# T01_Synth_Glove_v3_1.net
KiCad netlist of a schematic drawn in EAGLE
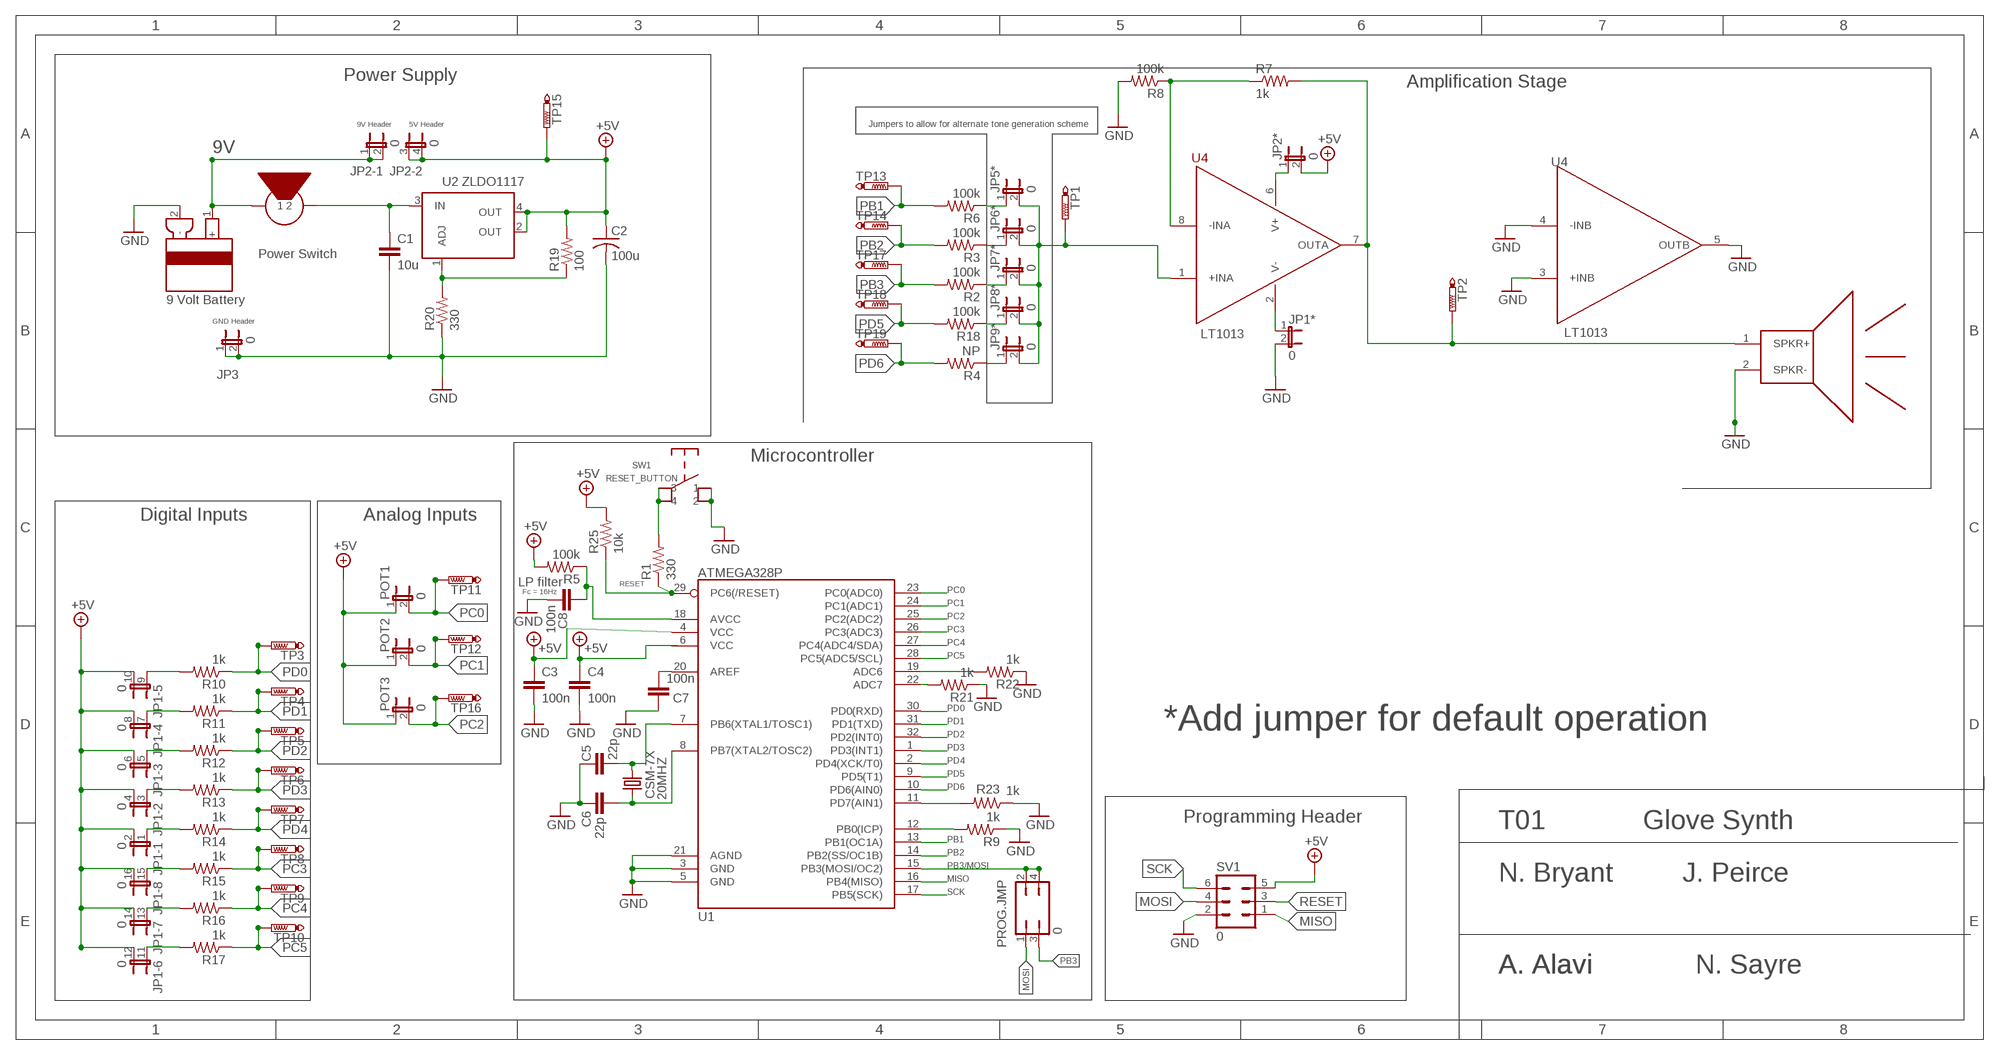
[diagram p0: schematic, sheet 1]

(export (version "E")
  (design (tool "Eeschema 10.0.6"))
  (components
    (comp (ref "20MHZ")
      (value "CSM-7X")
      (footprint "eagle-import:CSM-7X-DU")
      (libsource (lib "eagle-import") (part "CSM-7X-DU"))
    )
    (comp (ref "C1")
      (value "10u")
      (footprint "eagle-import:0603-CAP")
      (libsource (lib "eagle-import") (part "CAP0603-CAP"))
    )
    (comp (ref "C2")
      (value "100u")
      (footprint "eagle-import:C075-042X103")
      (libsource (lib "eagle-import") (part "C-US075-042X103"))
    )
    (comp (ref "C3")
      (value "100n")
      (footprint "eagle-import:0603-CAP")
      (libsource (lib "eagle-import") (part "CAP0603-CAP"))
    )
    (comp (ref "C4")
      (value "100n")
      (footprint "eagle-import:0603-CAP")
      (libsource (lib "eagle-import") (part "CAP0603-CAP"))
    )
    (comp (ref "C5")
      (value "22p")
      (footprint "eagle-import:0603-CAP")
      (libsource (lib "eagle-import") (part "CAP0603-CAP"))
    )
    (comp (ref "C6")
      (value "22p")
      (footprint "eagle-import:0603-CAP")
      (libsource (lib "eagle-import") (part "CAP0603-CAP"))
    )
    (comp (ref "C7")
      (value "100n")
      (footprint "eagle-import:0603-CAP")
      (libsource (lib "eagle-import") (part "CAP0603-CAP"))
    )
    (comp (ref "C8")
      (value "100n")
      (footprint "eagle-import:0603-CAP")
      (libsource (lib "eagle-import") (part "CAP0603-CAP"))
    )
    (comp (ref "JP1")
      (value "0")
      (footprint "eagle-import:JP8Q")
      (libsource (lib "eagle-import") (part "JP8QE"))
    )
    (comp (ref "JP1*")
      (value "0")
      (footprint "eagle-import:JP1")
      (libsource (lib "eagle-import") (part "JP1E"))
    )
    (comp (ref "JP2")
      (value "0")
      (footprint "eagle-import:JP2Q")
      (libsource (lib "eagle-import") (part "JP2QE"))
    )
    (comp (ref "JP2*")
      (value "0")
      (footprint "eagle-import:JP1")
      (libsource (lib "eagle-import") (part "JP1E"))
    )
    (comp (ref "JP3")
      (value "0")
      (footprint "eagle-import:JP1")
      (libsource (lib "eagle-import") (part "JP1E"))
    )
    (comp (ref "JP5*")
      (value "0")
      (footprint "eagle-import:JP1")
      (libsource (lib "eagle-import") (part "JP1E"))
    )
    (comp (ref "JP6*")
      (value "0")
      (footprint "eagle-import:JP1")
      (libsource (lib "eagle-import") (part "JP1E"))
    )
    (comp (ref "JP7*")
      (value "0")
      (footprint "eagle-import:JP1")
      (libsource (lib "eagle-import") (part "JP1E"))
    )
    (comp (ref "JP8*")
      (value "0")
      (footprint "eagle-import:JP1")
      (libsource (lib "eagle-import") (part "JP1E"))
    )
    (comp (ref "JP9*")
      (value "0")
      (footprint "eagle-import:JP1")
      (libsource (lib "eagle-import") (part "JP1E"))
    )
    (comp (ref "POT1")
      (value "0")
      (footprint "eagle-import:JP1")
      (libsource (lib "eagle-import") (part "JP1E"))
    )
    (comp (ref "POT2")
      (value "0")
      (footprint "eagle-import:JP1")
      (libsource (lib "eagle-import") (part "JP1E"))
    )
    (comp (ref "POT3")
      (value "0")
      (footprint "eagle-import:JP1")
      (libsource (lib "eagle-import") (part "JP1E"))
    )
    (comp (ref "PROG.JMP")
      (value "0")
      (footprint "eagle-import:JP2Q")
      (libsource (lib "eagle-import") (part "JP2Q"))
    )
    (comp (ref "R1")
      (value "330")
      (footprint "eagle-import:0603-RES")
      (libsource (lib "eagle-import") (part "RESISTOR0603"))
    )
    (comp (ref "R2")
      (value "100k")
      (footprint "eagle-import:0603-RES")
      (libsource (lib "eagle-import") (part "RESISTOR0603"))
    )
    (comp (ref "R3")
      (value "100k")
      (footprint "eagle-import:0603-RES")
      (libsource (lib "eagle-import") (part "RESISTOR0603"))
    )
    (comp (ref "R4")
      (value "NP")
      (footprint "eagle-import:0603-RES")
      (libsource (lib "eagle-import") (part "RESISTOR0603"))
    )
    (comp (ref "R5")
      (value "100k")
      (footprint "eagle-import:0603-RES")
      (libsource (lib "eagle-import") (part "RESISTOR0603"))
    )
    (comp (ref "R6")
      (value "100k")
      (footprint "eagle-import:0603-RES")
      (libsource (lib "eagle-import") (part "RESISTOR0603"))
    )
    (comp (ref "R7")
      (value "1k")
      (footprint "eagle-import:0603-RES")
      (libsource (lib "eagle-import") (part "RESISTOR0603"))
    )
    (comp (ref "R8")
      (value "100k")
      (footprint "eagle-import:0603-RES")
      (libsource (lib "eagle-import") (part "RESISTOR0603"))
    )
    (comp (ref "R9")
      (value "1k")
      (footprint "eagle-import:0603-RES")
      (libsource (lib "eagle-import") (part "RESISTOR0603"))
    )
    (comp (ref "R10")
      (value "1k")
      (footprint "eagle-import:0603-RES")
      (libsource (lib "eagle-import") (part "RESISTOR0603"))
    )
    (comp (ref "R11")
      (value "1k")
      (footprint "eagle-import:0603-RES")
      (libsource (lib "eagle-import") (part "RESISTOR0603"))
    )
    (comp (ref "R12")
      (value "1k")
      (footprint "eagle-import:0603-RES")
      (libsource (lib "eagle-import") (part "RESISTOR0603"))
    )
    (comp (ref "R13")
      (value "1k")
      (footprint "eagle-import:0603-RES")
      (libsource (lib "eagle-import") (part "RESISTOR0603"))
    )
    (comp (ref "R14")
      (value "1k")
      (footprint "eagle-import:0603-RES")
      (libsource (lib "eagle-import") (part "RESISTOR0603"))
    )
    (comp (ref "R15")
      (value "1k")
      (footprint "eagle-import:0603-RES")
      (libsource (lib "eagle-import") (part "RESISTOR0603"))
    )
    (comp (ref "R16")
      (value "1k")
      (footprint "eagle-import:0603-RES")
      (libsource (lib "eagle-import") (part "RESISTOR0603"))
    )
    (comp (ref "R17")
      (value "1k")
      (footprint "eagle-import:0603-RES")
      (libsource (lib "eagle-import") (part "RESISTOR0603"))
    )
    (comp (ref "R18")
      (value "100k")
      (footprint "eagle-import:0603-RES")
      (libsource (lib "eagle-import") (part "RESISTOR0603"))
    )
    (comp (ref "R19")
      (value "100")
      (footprint "eagle-import:0603-RES")
      (libsource (lib "eagle-import") (part "RESISTOR0603"))
    )
    (comp (ref "R20")
      (value "330")
      (footprint "eagle-import:0603-RES")
      (libsource (lib "eagle-import") (part "RESISTOR0603"))
    )
    (comp (ref "R21")
      (value "1k")
      (footprint "eagle-import:0603-RES")
      (libsource (lib "eagle-import") (part "RESISTOR0603"))
    )
    (comp (ref "R22")
      (value "1k")
      (footprint "eagle-import:0603-RES")
      (libsource (lib "eagle-import") (part "RESISTOR0603"))
    )
    (comp (ref "R23")
      (value "1k")
      (footprint "eagle-import:0603-RES")
      (libsource (lib "eagle-import") (part "RESISTOR0603"))
    )
    (comp (ref "R25")
      (value "10k")
      (footprint "eagle-import:0603-RES")
      (libsource (lib "eagle-import") (part "RESISTOR0603"))
    )
    (comp (ref "SV1")
      (value "0")
      (footprint "eagle-import:MA03-2")
      (libsource (lib "eagle-import") (part "MA03-2"))
    )
    (comp (ref "SW1")
      (value "RESET_BUTTON")
      (footprint "eagle-import:RESET_BUTTON")
      (libsource (lib "eagle-import") (part "RESET_BUTTON"))
    )
    (comp (ref "TP1")
      (value "PTR1B2,54")
      (footprint "eagle-import:B2,54")
      (libsource (lib "eagle-import") (part "PTR1B2,54"))
    )
    (comp (ref "TP2")
      (value "PTR1B2,54")
      (footprint "eagle-import:B2,54")
      (libsource (lib "eagle-import") (part "PTR1B2,54"))
    )
    (comp (ref "TP3")
      (value "PTR1B2,54")
      (footprint "eagle-import:B2,54")
      (libsource (lib "eagle-import") (part "PTR1B2,54"))
    )
    (comp (ref "TP4")
      (value "PTR1B2,54")
      (footprint "eagle-import:B2,54")
      (libsource (lib "eagle-import") (part "PTR1B2,54"))
    )
    (comp (ref "TP5")
      (value "PTR1B2,54")
      (footprint "eagle-import:B2,54")
      (libsource (lib "eagle-import") (part "PTR1B2,54"))
    )
    (comp (ref "TP6")
      (value "PTR1B2,54")
      (footprint "eagle-import:B2,54")
      (libsource (lib "eagle-import") (part "PTR1B2,54"))
    )
    (comp (ref "TP7")
      (value "PTR1B2,54")
      (footprint "eagle-import:B2,54")
      (libsource (lib "eagle-import") (part "PTR1B2,54"))
    )
    (comp (ref "TP8")
      (value "PTR1B2,54")
      (footprint "eagle-import:B2,54")
      (libsource (lib "eagle-import") (part "PTR1B2,54"))
    )
    (comp (ref "TP9")
      (value "PTR1B2,54")
      (footprint "eagle-import:B2,54")
      (libsource (lib "eagle-import") (part "PTR1B2,54"))
    )
    (comp (ref "TP10")
      (value "PTR1B2,54")
      (footprint "eagle-import:B2,54")
      (libsource (lib "eagle-import") (part "PTR1B2,54"))
    )
    (comp (ref "TP11")
      (value "PTR1B2,54")
      (footprint "eagle-import:B2,54")
      (libsource (lib "eagle-import") (part "PTR1B2,54"))
    )
    (comp (ref "TP12")
      (value "PTR1B2,54")
      (footprint "eagle-import:B2,54")
      (libsource (lib "eagle-import") (part "PTR1B2,54"))
    )
    (comp (ref "TP13")
      (value "PTR1B2,54")
      (footprint "eagle-import:B2,54")
      (libsource (lib "eagle-import") (part "PTR1B2,54"))
    )
    (comp (ref "TP14")
      (value "PTR1B2,54")
      (footprint "eagle-import:B2,54")
      (libsource (lib "eagle-import") (part "PTR1B2,54"))
    )
    (comp (ref "TP15")
      (value "PTR1B2,54")
      (footprint "eagle-import:B2,54")
      (libsource (lib "eagle-import") (part "PTR1B2,54"))
    )
    (comp (ref "TP16")
      (value "PTR1B2,54")
      (footprint "eagle-import:B2,54")
      (libsource (lib "eagle-import") (part "PTR1B2,54"))
    )
    (comp (ref "TP17")
      (value "PTR1B2,54")
      (footprint "eagle-import:B2,54")
      (libsource (lib "eagle-import") (part "PTR1B2,54"))
    )
    (comp (ref "TP18")
      (value "PTR1B2,54")
      (footprint "eagle-import:B2,54")
      (libsource (lib "eagle-import") (part "PTR1B2,54"))
    )
    (comp (ref "TP19")
      (value "PTR1B2,54")
      (footprint "eagle-import:B2,54")
      (libsource (lib "eagle-import") (part "PTR1B2,54"))
    )
    (comp (ref "U$1")
      (value "SPEAKER")
      (footprint "eagle-import:JP1")
      (libsource (lib "eagle-import") (part "SPEAKER"))
    )
    (comp (ref "U$7")
      (value "POWER_SWITCH")
      (footprint "eagle-import:JP1")
      (libsource (lib "eagle-import") (part "POWER_SWITCH"))
    )
    (comp (ref "U$8")
      (value "9VOLTBATTERY")
      (footprint "eagle-import:JP1")
      (libsource (lib "eagle-import") (part "9VOLTBATTERY"))
    )
    (comp (ref "U1")
      (value "ATMEGA328P")
      (footprint "eagle-import:TQFP32-08")
      (libsource (lib "eagle-import") (part "ATMEGA328_SMT"))
    )
    (comp (ref "U2")
      (value "ZLDO1117")
      (footprint "eagle-import:SOT223")
      (libsource (lib "eagle-import") (part "ZLDO1117"))
    )
    (comp (ref "U4")
      (value "LT1013")
      (footprint "eagle-import:SO08")
      (libsource (lib "eagle-import") (part "LT1013"))
    )
  )
  (nets
    (net (code "1") (name "+5V") (class "Default")
      (node (ref "C2") (pin "1") (pinfunction "1_1") (pintype "passive"))
      (node (ref "C3") (pin "1") (pinfunction "1_1") (pintype "passive"))
      (node (ref "C4") (pin "1") (pinfunction "1_1") (pintype "passive"))
      (node (ref "JP1") (pin "10") (pinfunction "2_10") (pintype "passive"))
      (node (ref "JP1") (pin "12") (pinfunction "2_12") (pintype "passive"))
      (node (ref "JP1") (pin "14") (pinfunction "2_14") (pintype "passive"))
      (node (ref "JP1") (pin "16") (pinfunction "2_16") (pintype "passive"))
      (node (ref "JP1") (pin "2") (pinfunction "2_2") (pintype "passive"))
      (node (ref "JP1") (pin "4") (pinfunction "2_4") (pintype "passive"))
      (node (ref "JP1") (pin "6") (pinfunction "2_6") (pintype "passive"))
      (node (ref "JP1") (pin "8") (pinfunction "2_8") (pintype "passive"))
      (node (ref "JP2") (pin "3") (pinfunction "1_3") (pintype "passive"))
      (node (ref "JP2") (pin "4") (pinfunction "2_4") (pintype "passive"))
      (node (ref "JP2*") (pin "2") (pinfunction "2_2") (pintype "passive"))
      (node (ref "POT1") (pin "1") (pinfunction "1_1") (pintype "passive"))
      (node (ref "POT2") (pin "1") (pinfunction "1_1") (pintype "passive"))
      (node (ref "POT3") (pin "1") (pinfunction "1_1") (pintype "passive"))
      (node (ref "R19") (pin "2") (pinfunction "2_2") (pintype "passive"))
      (node (ref "R25") (pin "2") (pinfunction "2_2") (pintype "passive"))
      (node (ref "R5") (pin "2") (pinfunction "2_2") (pintype "passive"))
      (node (ref "SV1") (pin "5") (pinfunction "5_5") (pintype "passive"))
      (node (ref "TP15") (pin "TP") (pinfunction "TP_TP") (pintype "input"))
      (node (ref "U1") (pin "4") (pinfunction "VCC_4") (pintype "bidirectional"))
      (node (ref "U2") (pin "2") (pinfunction "OUT_2") (pintype "bidirectional"))
      (node (ref "U2") (pin "4") (pinfunction "OUT_4") (pintype "bidirectional"))
    )
    (net (code "2") (name "/9V") (class "Default")
      (node (ref "JP2") (pin "1") (pinfunction "1_1") (pintype "passive"))
      (node (ref "JP2") (pin "2") (pinfunction "2_2") (pintype "passive"))
      (node (ref "U$7") (pin "1") (pinfunction "1_1") (pintype "bidirectional"))
      (node (ref "U$8") (pin "1") (pinfunction "+_1") (pintype "bidirectional"))
    )
    (net (code "3") (name "/PB3{slash}MOSI") (class "Default")
      (node (ref "PROG.JMP") (pin "2") (pinfunction "2_2") (pintype "passive"))
      (node (ref "PROG.JMP") (pin "4") (pinfunction "4_4") (pintype "passive"))
      (node (ref "U1") (pin "15") (pinfunction "PB3(MOSI/OC2)_15") (pintype "bidirectional"))
    )
    (net (code "4") (name "GND") (class "Default")
      (node (ref "C1") (pin "2") (pinfunction "2_2") (pintype "passive"))
      (node (ref "C2") (pin "2") (pinfunction "2_2") (pintype "passive"))
      (node (ref "C3") (pin "2") (pinfunction "2_2") (pintype "passive"))
      (node (ref "C4") (pin "2") (pinfunction "2_2") (pintype "passive"))
      (node (ref "C5") (pin "2") (pinfunction "2_2") (pintype "passive"))
      (node (ref "C6") (pin "2") (pinfunction "2_2") (pintype "passive"))
      (node (ref "C7") (pin "2") (pinfunction "2_2") (pintype "passive"))
      (node (ref "C8") (pin "2") (pinfunction "2_2") (pintype "passive"))
      (node (ref "JP1*") (pin "2") (pinfunction "2_2") (pintype "passive"))
      (node (ref "JP3") (pin "1") (pinfunction "1_1") (pintype "passive"))
      (node (ref "JP3") (pin "2") (pinfunction "2_2") (pintype "passive"))
      (node (ref "R20") (pin "1") (pinfunction "1_1") (pintype "passive"))
      (node (ref "R21") (pin "1") (pinfunction "1_1") (pintype "passive"))
      (node (ref "R22") (pin "1") (pinfunction "1_1") (pintype "passive"))
      (node (ref "R23") (pin "1") (pinfunction "1_1") (pintype "passive"))
      (node (ref "R8") (pin "2") (pinfunction "2_2") (pintype "passive"))
      (node (ref "R9") (pin "1") (pinfunction "1_1") (pintype "passive"))
      (node (ref "SV1") (pin "2") (pinfunction "2_2") (pintype "passive"))
      (node (ref "SW1") (pin "1") (pinfunction "1_1") (pintype "bidirectional"))
      (node (ref "SW1") (pin "2") (pinfunction "2_2") (pintype "bidirectional"))
      (node (ref "U$1") (pin "2") (pinfunction "SPKR-_2") (pintype "bidirectional"))
      (node (ref "U$8") (pin "2") (pinfunction "-_2") (pintype "bidirectional"))
      (node (ref "U1") (pin "21") (pinfunction "AGND_21") (pintype "bidirectional"))
      (node (ref "U1") (pin "3") (pinfunction "GND_3") (pintype "bidirectional"))
      (node (ref "U1") (pin "5") (pinfunction "GND_5") (pintype "bidirectional"))
      (node (ref "U4") (pin "3") (pinfunction "+INB_3") (pintype "bidirectional"))
      (node (ref "U4") (pin "4") (pinfunction "-INB_4") (pintype "bidirectional"))
      (node (ref "U4") (pin "5") (pinfunction "OUTB_5") (pintype "bidirectional"))
    )
    (net (code "5") (name "MISO") (class "Default")
      (node (ref "SV1") (pin "1") (pinfunction "1_1") (pintype "passive"))
      (node (ref "U1") (pin "16") (pinfunction "PB4(MISO)_16") (pintype "bidirectional"))
    )
    (net (code "6") (name "MOSI") (class "Default")
      (node (ref "PROG.JMP") (pin "1") (pinfunction "1_1") (pintype "passive"))
      (node (ref "SV1") (pin "4") (pinfunction "4_4") (pintype "passive"))
    )
    (net (code "7") (name "Net-(JP1-Pad1)") (class "Default")
      (node (ref "JP1") (pin "1") (pinfunction "1_1") (pintype "passive"))
      (node (ref "R14") (pin "2") (pinfunction "2_2") (pintype "passive"))
    )
    (net (code "8") (name "Net-(JP1B-1)") (class "Default")
      (node (ref "JP1") (pin "3") (pinfunction "1_3") (pintype "passive"))
      (node (ref "R13") (pin "2") (pinfunction "2_2") (pintype "passive"))
    )
    (net (code "9") (name "Net-(JP1C-1)") (class "Default")
      (node (ref "JP1") (pin "5") (pinfunction "1_5") (pintype "passive"))
      (node (ref "R12") (pin "2") (pinfunction "2_2") (pintype "passive"))
    )
    (net (code "10") (name "Net-(JP1D-1)") (class "Default")
      (node (ref "JP1") (pin "7") (pinfunction "1_7") (pintype "passive"))
      (node (ref "R11") (pin "2") (pinfunction "2_2") (pintype "passive"))
    )
    (net (code "11") (name "Net-(JP1E-1)") (class "Default")
      (node (ref "JP1") (pin "9") (pinfunction "1_9") (pintype "passive"))
      (node (ref "R10") (pin "2") (pinfunction "2_2") (pintype "passive"))
    )
    (net (code "12") (name "Net-(JP1F-1)") (class "Default")
      (node (ref "JP1") (pin "11") (pinfunction "1_11") (pintype "passive"))
      (node (ref "R17") (pin "2") (pinfunction "2_2") (pintype "passive"))
    )
    (net (code "13") (name "Net-(JP1G-1)") (class "Default")
      (node (ref "JP1") (pin "13") (pinfunction "1_13") (pintype "passive"))
      (node (ref "R16") (pin "2") (pinfunction "2_2") (pintype "passive"))
    )
    (net (code "14") (name "Net-(JP1H-1)") (class "Default")
      (node (ref "JP1") (pin "15") (pinfunction "1_15") (pintype "passive"))
      (node (ref "R15") (pin "2") (pinfunction "2_2") (pintype "passive"))
    )
    (net (code "15") (name "Net-(JP5*-Pad1)") (class "Default")
      (node (ref "JP5*") (pin "1") (pinfunction "1_1") (pintype "passive"))
      (node (ref "R6") (pin "1") (pinfunction "1_1") (pintype "passive"))
    )
    (net (code "16") (name "Net-(JP6*-Pad1)") (class "Default")
      (node (ref "JP6*") (pin "1") (pinfunction "1_1") (pintype "passive"))
      (node (ref "R3") (pin "1") (pinfunction "1_1") (pintype "passive"))
    )
    (net (code "17") (name "Net-(JP7*-Pad1)") (class "Default")
      (node (ref "JP7*") (pin "1") (pinfunction "1_1") (pintype "passive"))
      (node (ref "R2") (pin "1") (pinfunction "1_1") (pintype "passive"))
    )
    (net (code "18") (name "Net-(JP8*-Pad1)") (class "Default")
      (node (ref "JP8*") (pin "1") (pinfunction "1_1") (pintype "passive"))
      (node (ref "R18") (pin "1") (pinfunction "1_1") (pintype "passive"))
    )
    (net (code "19") (name "Net-(JP9*-Pad1)") (class "Default")
      (node (ref "JP9*") (pin "1") (pinfunction "1_1") (pintype "passive"))
      (node (ref "R4") (pin "1") (pinfunction "1_1") (pintype "passive"))
    )
    (net (code "20") (name "Net-(R1-Pad2)") (class "Default")
      (node (ref "R1") (pin "2") (pinfunction "2_2") (pintype "passive"))
      (node (ref "SW1") (pin "3") (pinfunction "3_3") (pintype "bidirectional"))
      (node (ref "SW1") (pin "4") (pinfunction "4_4") (pintype "bidirectional"))
    )
    (net (code "21") (name "Net-(U$1-SPKR+)") (class "Default")
      (node (ref "R7") (pin "2") (pinfunction "2_2") (pintype "passive"))
      (node (ref "TP2") (pin "TP") (pinfunction "TP_TP") (pintype "input"))
      (node (ref "U$1") (pin "1") (pinfunction "SPKR+_1") (pintype "bidirectional"))
      (node (ref "U4") (pin "7") (pinfunction "OUTA_7") (pintype "bidirectional"))
    )
    (net (code "22") (name "Net-(U1-ADC6)") (class "Default")
      (node (ref "R22") (pin "2") (pinfunction "2_2") (pintype "passive"))
      (node (ref "U1") (pin "19") (pinfunction "ADC6_19") (pintype "bidirectional"))
    )
    (net (code "23") (name "Net-(U1-ADC7)") (class "Default")
      (node (ref "R21") (pin "2") (pinfunction "2_2") (pintype "passive"))
      (node (ref "U1") (pin "22") (pinfunction "ADC7_22") (pintype "bidirectional"))
    )
    (net (code "24") (name "Net-(U1-AREF)") (class "Default")
      (node (ref "C7") (pin "1") (pinfunction "1_1") (pintype "passive"))
      (node (ref "U1") (pin "20") (pinfunction "AREF_20") (pintype "bidirectional"))
    )
    (net (code "25") (name "Net-(U1-AVCC)") (class "Default")
      (node (ref "C8") (pin "1") (pinfunction "1_1") (pintype "passive"))
      (node (ref "R5") (pin "1") (pinfunction "1_1") (pintype "passive"))
      (node (ref "U1") (pin "18") (pinfunction "AVCC_18") (pintype "bidirectional"))
    )
    (net (code "26") (name "Net-(U1-PB0(ICP))") (class "Default")
      (node (ref "R9") (pin "2") (pinfunction "2_2") (pintype "passive"))
      (node (ref "U1") (pin "12") (pinfunction "PB0(ICP)_12") (pintype "bidirectional"))
    )
    (net (code "27") (name "Net-(U1-PB6(XTAL1{slash}TOSC1))") (class "Default")
      (node (ref "20MHZ") (pin "1") (pinfunction "1_1") (pintype "passive"))
      (node (ref "C5") (pin "1") (pinfunction "1_1") (pintype "passive"))
      (node (ref "U1") (pin "7") (pinfunction "PB6(XTAL1/TOSC1)_7") (pintype "bidirectional"))
    )
    (net (code "28") (name "Net-(U1-PB7(XTAL2{slash}TOSC2))") (class "Default")
      (node (ref "20MHZ") (pin "2") (pinfunction "2_2") (pintype "passive"))
      (node (ref "C6") (pin "1") (pinfunction "1_1") (pintype "passive"))
      (node (ref "U1") (pin "8") (pinfunction "PB7(XTAL2/TOSC2)_8") (pintype "bidirectional"))
    )
    (net (code "29") (name "Net-(U1-PD7(AIN1))") (class "Default")
      (node (ref "R23") (pin "2") (pinfunction "2_2") (pintype "passive"))
      (node (ref "U1") (pin "11") (pinfunction "PD7(AIN1)_11") (pintype "bidirectional"))
    )
    (net (code "30") (name "Net-(U2-ADJ)") (class "Default")
      (node (ref "R19") (pin "1") (pinfunction "1_1") (pintype "passive"))
      (node (ref "R20") (pin "2") (pinfunction "2_2") (pintype "passive"))
      (node (ref "U2") (pin "1") (pinfunction "ADJ_1") (pintype "bidirectional"))
    )
    (net (code "31") (name "Net-(U2-IN)") (class "Default")
      (node (ref "C1") (pin "1") (pinfunction "1_1") (pintype "passive"))
      (node (ref "U$7") (pin "2") (pinfunction "2_2") (pintype "bidirectional"))
      (node (ref "U2") (pin "3") (pinfunction "IN_3") (pintype "bidirectional"))
    )
    (net (code "32") (name "Net-(U4-+INA)") (class "Default")
      (node (ref "JP5*") (pin "2") (pinfunction "2_2") (pintype "passive"))
      (node (ref "JP6*") (pin "2") (pinfunction "2_2") (pintype "passive"))
      (node (ref "JP7*") (pin "2") (pinfunction "2_2") (pintype "passive"))
      (node (ref "JP8*") (pin "2") (pinfunction "2_2") (pintype "passive"))
      (node (ref "JP9*") (pin "2") (pinfunction "2_2") (pintype "passive"))
      (node (ref "TP1") (pin "TP") (pinfunction "TP_TP") (pintype "input"))
      (node (ref "U4") (pin "1") (pinfunction "+INA_1") (pintype "bidirectional"))
    )
    (net (code "33") (name "Net-(U4--INA)") (class "Default")
      (node (ref "R7") (pin "1") (pinfunction "1_1") (pintype "passive"))
      (node (ref "R8") (pin "1") (pinfunction "1_1") (pintype "passive"))
      (node (ref "U4") (pin "8") (pinfunction "-INA_8") (pintype "bidirectional"))
    )
    (net (code "34") (name "Net-(U4-V+)") (class "Default")
      (node (ref "JP2*") (pin "1") (pinfunction "1_1") (pintype "passive"))
      (node (ref "U4") (pin "6") (pinfunction "V+_6") (pintype "power_in"))
    )
    (net (code "35") (name "Net-(U4-V-)") (class "Default")
      (node (ref "JP1*") (pin "1") (pinfunction "1_1") (pintype "passive"))
      (node (ref "U4") (pin "2") (pinfunction "V-_2") (pintype "power_in"))
    )
    (net (code "36") (name "PB1") (class "Default")
      (node (ref "R6") (pin "2") (pinfunction "2_2") (pintype "passive"))
      (node (ref "TP13") (pin "TP") (pinfunction "TP_TP") (pintype "input"))
      (node (ref "U1") (pin "13") (pinfunction "PB1(OC1A)_13") (pintype "bidirectional"))
    )
    (net (code "37") (name "PB2") (class "Default")
      (node (ref "R3") (pin "2") (pinfunction "2_2") (pintype "passive"))
      (node (ref "TP14") (pin "TP") (pinfunction "TP_TP") (pintype "input"))
      (node (ref "U1") (pin "14") (pinfunction "PB2(SS/OC1B)_14") (pintype "bidirectional"))
    )
    (net (code "38") (name "PB3") (class "Default")
      (node (ref "PROG.JMP") (pin "3") (pinfunction "3_3") (pintype "passive"))
      (node (ref "R2") (pin "2") (pinfunction "2_2") (pintype "passive"))
      (node (ref "TP17") (pin "TP") (pinfunction "TP_TP") (pintype "input"))
    )
    (net (code "39") (name "PC0") (class "Default")
      (node (ref "POT1") (pin "2") (pinfunction "2_2") (pintype "passive"))
      (node (ref "TP11") (pin "TP") (pinfunction "TP_TP") (pintype "input"))
      (node (ref "U1") (pin "23") (pinfunction "PC0(ADC0)_23") (pintype "bidirectional"))
    )
    (net (code "40") (name "PC1") (class "Default")
      (node (ref "POT2") (pin "2") (pinfunction "2_2") (pintype "passive"))
      (node (ref "TP12") (pin "TP") (pinfunction "TP_TP") (pintype "input"))
      (node (ref "U1") (pin "24") (pinfunction "PC1(ADC1)_24") (pintype "bidirectional"))
    )
    (net (code "41") (name "PC2") (class "Default")
      (node (ref "POT3") (pin "2") (pinfunction "2_2") (pintype "passive"))
      (node (ref "TP16") (pin "TP") (pinfunction "TP_TP") (pintype "input"))
      (node (ref "U1") (pin "25") (pinfunction "PC2(ADC2)_25") (pintype "bidirectional"))
    )
    (net (code "42") (name "PC3") (class "Default")
      (node (ref "R15") (pin "1") (pinfunction "1_1") (pintype "passive"))
      (node (ref "TP8") (pin "TP") (pinfunction "TP_TP") (pintype "input"))
      (node (ref "U1") (pin "26") (pinfunction "PC3(ADC3)_26") (pintype "bidirectional"))
    )
    (net (code "43") (name "PC4") (class "Default")
      (node (ref "R16") (pin "1") (pinfunction "1_1") (pintype "passive"))
      (node (ref "TP9") (pin "TP") (pinfunction "TP_TP") (pintype "input"))
      (node (ref "U1") (pin "27") (pinfunction "PC4(ADC4/SDA)_27") (pintype "bidirectional"))
    )
    (net (code "44") (name "PC5") (class "Default")
      (node (ref "R17") (pin "1") (pinfunction "1_1") (pintype "passive"))
      (node (ref "TP10") (pin "TP") (pinfunction "TP_TP") (pintype "input"))
      (node (ref "U1") (pin "28") (pinfunction "PC5(ADC5/SCL)_28") (pintype "bidirectional"))
    )
    (net (code "45") (name "PD0") (class "Default")
      (node (ref "R10") (pin "1") (pinfunction "1_1") (pintype "passive"))
      (node (ref "TP3") (pin "TP") (pinfunction "TP_TP") (pintype "input"))
      (node (ref "U1") (pin "30") (pinfunction "PD0(RXD)_30") (pintype "bidirectional"))
    )
    (net (code "46") (name "PD1") (class "Default")
      (node (ref "R11") (pin "1") (pinfunction "1_1") (pintype "passive"))
      (node (ref "TP4") (pin "TP") (pinfunction "TP_TP") (pintype "input"))
      (node (ref "U1") (pin "31") (pinfunction "PD1(TXD)_31") (pintype "bidirectional"))
    )
    (net (code "47") (name "PD2") (class "Default")
      (node (ref "R12") (pin "1") (pinfunction "1_1") (pintype "passive"))
      (node (ref "TP5") (pin "TP") (pinfunction "TP_TP") (pintype "input"))
      (node (ref "U1") (pin "32") (pinfunction "PD2(INT0)_32") (pintype "bidirectional"))
    )
    (net (code "48") (name "PD3") (class "Default")
      (node (ref "R13") (pin "1") (pinfunction "1_1") (pintype "passive"))
      (node (ref "TP6") (pin "TP") (pinfunction "TP_TP") (pintype "input"))
      (node (ref "U1") (pin "1") (pinfunction "PD3(INT1)_1") (pintype "bidirectional"))
    )
    (net (code "49") (name "PD4") (class "Default")
      (node (ref "R14") (pin "1") (pinfunction "1_1") (pintype "passive"))
      (node (ref "TP7") (pin "TP") (pinfunction "TP_TP") (pintype "input"))
      (node (ref "U1") (pin "2") (pinfunction "PD4(XCK/T0)_2") (pintype "bidirectional"))
    )
    (net (code "50") (name "PD5") (class "Default")
      (node (ref "R18") (pin "2") (pinfunction "2_2") (pintype "passive"))
      (node (ref "TP18") (pin "TP") (pinfunction "TP_TP") (pintype "input"))
      (node (ref "U1") (pin "9") (pinfunction "PD5(T1)_9") (pintype "bidirectional"))
    )
    (net (code "51") (name "PD6") (class "Default")
      (node (ref "R4") (pin "2") (pinfunction "2_2") (pintype "passive"))
      (node (ref "TP19") (pin "TP") (pinfunction "TP_TP") (pintype "input"))
      (node (ref "U1") (pin "10") (pinfunction "PD6(AIN0)_10") (pintype "bidirectional"))
    )
    (net (code "52") (name "RESET") (class "Default")
      (node (ref "R1") (pin "1") (pinfunction "1_1") (pintype "passive"))
      (node (ref "R25") (pin "1") (pinfunction "1_1") (pintype "passive"))
      (node (ref "SV1") (pin "3") (pinfunction "3_3") (pintype "passive"))
      (node (ref "U1") (pin "29") (pinfunction "PC6(/RESET)_29") (pintype "bidirectional"))
    )
    (net (code "53") (name "SCK") (class "Default")
      (node (ref "SV1") (pin "6") (pinfunction "6_6") (pintype "passive"))
      (node (ref "U1") (pin "17") (pinfunction "PB5(SCK)_17") (pintype "bidirectional"))
    )
    (net (code "54") (name "unconnected-(U1-VCC-Pad6)") (class "Default")
      (node (ref "U1") (pin "6") (pinfunction "VCC_6") (pintype "bidirectional"))
    )
  )
)
